# MB1297_Arduino.net
KiCad netlist of a schematic drawn in Altium Designer
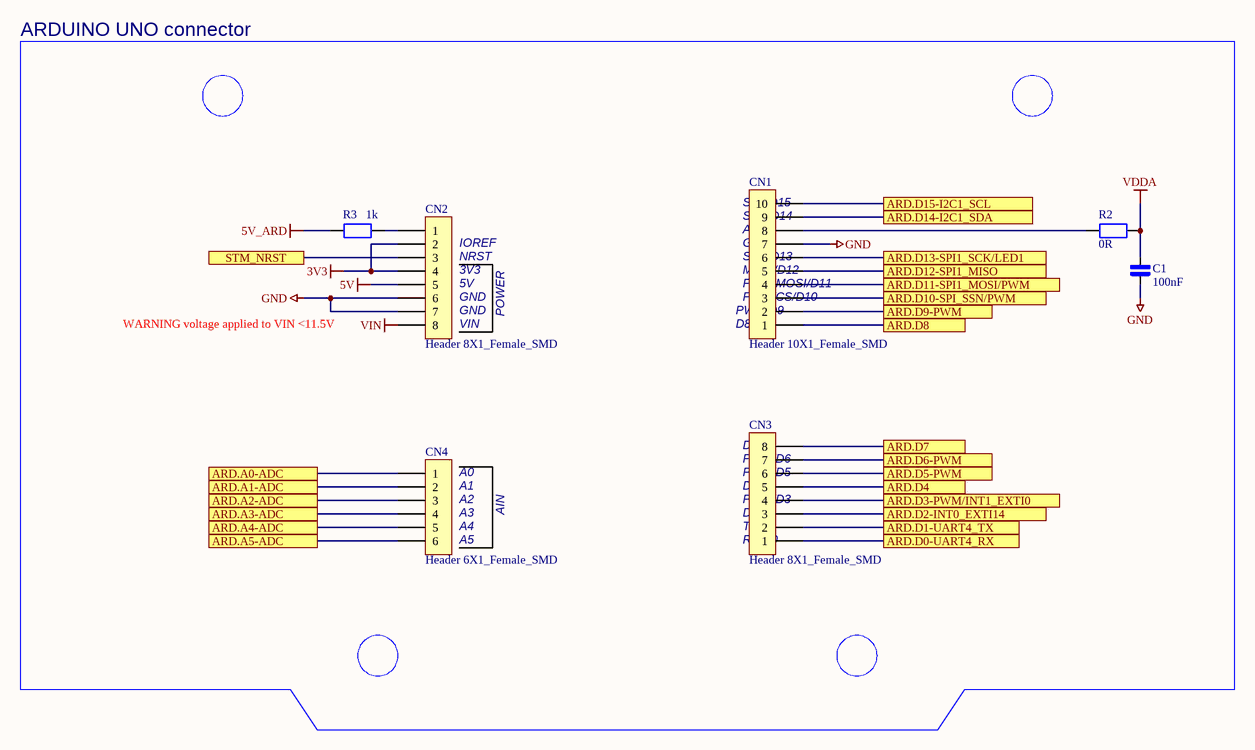
[diagram p0: MB1297_Arduino.SchDoc]

(export (version "E")
  (design (tool "Eeschema 10.0.6"))
  (components
    (comp (ref "C1")
      (value "100nF")
      (footprint "0402")
      (description "Capacitor_not polarized")
      (libsource (lib "ST_Lib3D") (part "CAP_NPOL"))
    )
    (comp (ref "CN1")
      (value "Header 10X1_Female_SMD")
      (footprint "F-V50XC-1X10R-LF")
      (description "Header, 10-Pin, SMD, Single row,female")
      (fields (field (name "PUBLISHER") "Altium Limited"))
      (libsource (lib "ST_Lib3D") (part "Header 10X1_Female_SMD"))
    )
    (comp (ref "CN2")
      (value "Header 8X1_Female_SMD")
      (footprint "F-V50XC-1X08R-LF")
      (description "Header, 8-Pin, SMD, Single row,female")
      (fields (field (name "PUBLISHER") "Altium Limited"))
      (libsource (lib "ST_Lib3D") (part "Header 8X1_Female_SMD"))
    )
    (comp (ref "CN3")
      (value "Header 8X1_Female_SMD")
      (footprint "F-V50XC-1X08R-LF")
      (description "Header, 8-Pin, SMD, Single row,female")
      (fields (field (name "PUBLISHER") "Altium Limited"))
      (libsource (lib "") (part "Header 8X1_Female_SMD_1"))
    )
    (comp (ref "CN4")
      (value "Header 6X1_Female_SMD")
      (footprint "F-V50XC-1X06R-LF")
      (description "Header, 6-Pin, SMD, Single row,female")
      (fields (field (name "PUBLISHER") "Altium Limited"))
      (libsource (lib "ST_Lib3D") (part "Header 6X1_Female_SMD"))
    )
    (comp (ref "R2")
      (value "0R")
      (footprint "0402")
      (description "Resistor")
      (libsource (lib "Lib3D_Altium10_Schlib") (part "RES"))
    )
    (comp (ref "R3")
      (value "1k")
      (footprint "0402")
      (description "Resistor")
      (libsource (lib "Lib3D_Altium10_Schlib") (part "RES"))
    )
  )
  (nets
    (net (code "1") (name "/ARD.A0-ADC") (class "Default")
      (node (ref "CN4") (pin "1") (pinfunction "1_1") (pintype "passive"))
    )
    (net (code "2") (name "/ARD.A1-ADC") (class "Default")
      (node (ref "CN4") (pin "2") (pinfunction "2_2") (pintype "passive"))
    )
    (net (code "3") (name "/ARD.A2-ADC") (class "Default")
      (node (ref "CN4") (pin "3") (pinfunction "3_3") (pintype "passive"))
    )
    (net (code "4") (name "/ARD.A3-ADC") (class "Default")
      (node (ref "CN4") (pin "4") (pinfunction "4_4") (pintype "passive"))
    )
    (net (code "5") (name "/ARD.A4-ADC") (class "Default")
      (node (ref "CN4") (pin "5") (pinfunction "5_5") (pintype "passive"))
    )
    (net (code "6") (name "/ARD.A5-ADC") (class "Default")
      (node (ref "CN4") (pin "6") (pinfunction "6_6") (pintype "passive"))
    )
    (net (code "7") (name "/ARD.D0-UART4_RX") (class "Default")
      (node (ref "CN3") (pin "1") (pinfunction "1_1") (pintype "passive"))
    )
    (net (code "8") (name "/ARD.D1-UART4_TX") (class "Default")
      (node (ref "CN3") (pin "2") (pinfunction "2_2") (pintype "passive"))
    )
    (net (code "9") (name "/ARD.D2-INT0_EXTI14") (class "Default")
      (node (ref "CN3") (pin "3") (pinfunction "3_3") (pintype "passive"))
    )
    (net (code "10") (name "/ARD.D3-PWM{slash}INT1_EXTI0") (class "Default")
      (node (ref "CN3") (pin "4") (pinfunction "4_4") (pintype "passive"))
    )
    (net (code "11") (name "/ARD.D4") (class "Default")
      (node (ref "CN3") (pin "5") (pinfunction "5_5") (pintype "passive"))
    )
    (net (code "12") (name "/ARD.D5-PWM") (class "Default")
      (node (ref "CN3") (pin "6") (pinfunction "6_6") (pintype "passive"))
    )
    (net (code "13") (name "/ARD.D6-PWM") (class "Default")
      (node (ref "CN3") (pin "7") (pinfunction "7_7") (pintype "passive"))
    )
    (net (code "14") (name "/ARD.D7") (class "Default")
      (node (ref "CN3") (pin "8") (pinfunction "8_8") (pintype "passive"))
    )
    (net (code "15") (name "/ARD.D8") (class "Default")
      (node (ref "CN1") (pin "1") (pinfunction "1_1") (pintype "passive"))
    )
    (net (code "16") (name "/ARD.D9-PWM") (class "Default")
      (node (ref "CN1") (pin "2") (pinfunction "2_2") (pintype "passive"))
    )
    (net (code "17") (name "/ARD.D10-SPI_SSN{slash}PWM") (class "Default")
      (node (ref "CN1") (pin "3") (pinfunction "3_3") (pintype "passive"))
    )
    (net (code "18") (name "/ARD.D11-SPI1_MOSI{slash}PWM") (class "Default")
      (node (ref "CN1") (pin "4") (pinfunction "4_4") (pintype "passive"))
    )
    (net (code "19") (name "/ARD.D12-SPI1_MISO") (class "Default")
      (node (ref "CN1") (pin "5") (pinfunction "5_5") (pintype "passive"))
    )
    (net (code "20") (name "/ARD.D13-SPI1_SCK{slash}LED1") (class "Default")
      (node (ref "CN1") (pin "6") (pinfunction "6_6") (pintype "passive"))
    )
    (net (code "21") (name "/ARD.D14-I2C1_SDA") (class "Default")
      (node (ref "CN1") (pin "9") (pinfunction "9_9") (pintype "passive"))
    )
    (net (code "22") (name "/ARD.D15-I2C1_SCL") (class "Default")
      (node (ref "CN1") (pin "10") (pinfunction "10_10") (pintype "passive"))
    )
    (net (code "23") (name "/STM_NRST") (class "Default")
      (node (ref "CN2") (pin "3") (pinfunction "3_3") (pintype "passive"))
    )
    (net (code "24") (name "3V3") (class "Default")
      (node (ref "CN2") (pin "2") (pinfunction "2_2") (pintype "passive"))
      (node (ref "CN2") (pin "4") (pinfunction "4_4") (pintype "passive"))
    )
    (net (code "25") (name "5V") (class "Default")
      (node (ref "CN2") (pin "5") (pinfunction "5_5") (pintype "passive"))
    )
    (net (code "26") (name "5V_ARD") (class "Default")
      (node (ref "R3") (pin "1") (pinfunction "1_1") (pintype "passive"))
    )
    (net (code "27") (name "GND") (class "Default")
      (node (ref "C1") (pin "2") (pinfunction "2_2") (pintype "passive"))
      (node (ref "CN1") (pin "7") (pinfunction "7_7") (pintype "passive"))
      (node (ref "CN2") (pin "6") (pinfunction "6_6") (pintype "passive"))
      (node (ref "CN2") (pin "7") (pinfunction "7_7") (pintype "passive"))
    )
    (net (code "28") (name "Net-(CN1-Pad8)") (class "Default")
      (node (ref "CN1") (pin "8") (pinfunction "8_8") (pintype "passive"))
      (node (ref "R2") (pin "1") (pinfunction "1_1") (pintype "passive"))
    )
    (net (code "29") (name "Net-(CN2-Pad1)") (class "Default")
      (node (ref "CN2") (pin "1") (pinfunction "1_1") (pintype "passive"))
      (node (ref "R3") (pin "2") (pinfunction "2_2") (pintype "passive"))
    )
    (net (code "30") (name "VDDA") (class "Default")
      (node (ref "C1") (pin "1") (pinfunction "1_1") (pintype "passive"))
      (node (ref "R2") (pin "2") (pinfunction "2_2") (pintype "passive"))
    )
    (net (code "31") (name "VIN") (class "Default")
      (node (ref "CN2") (pin "8") (pinfunction "8_8") (pintype "passive"))
    )
  )
)
